# Output_channel.net
KiCad netlist of a schematic drawn in Altium Designer
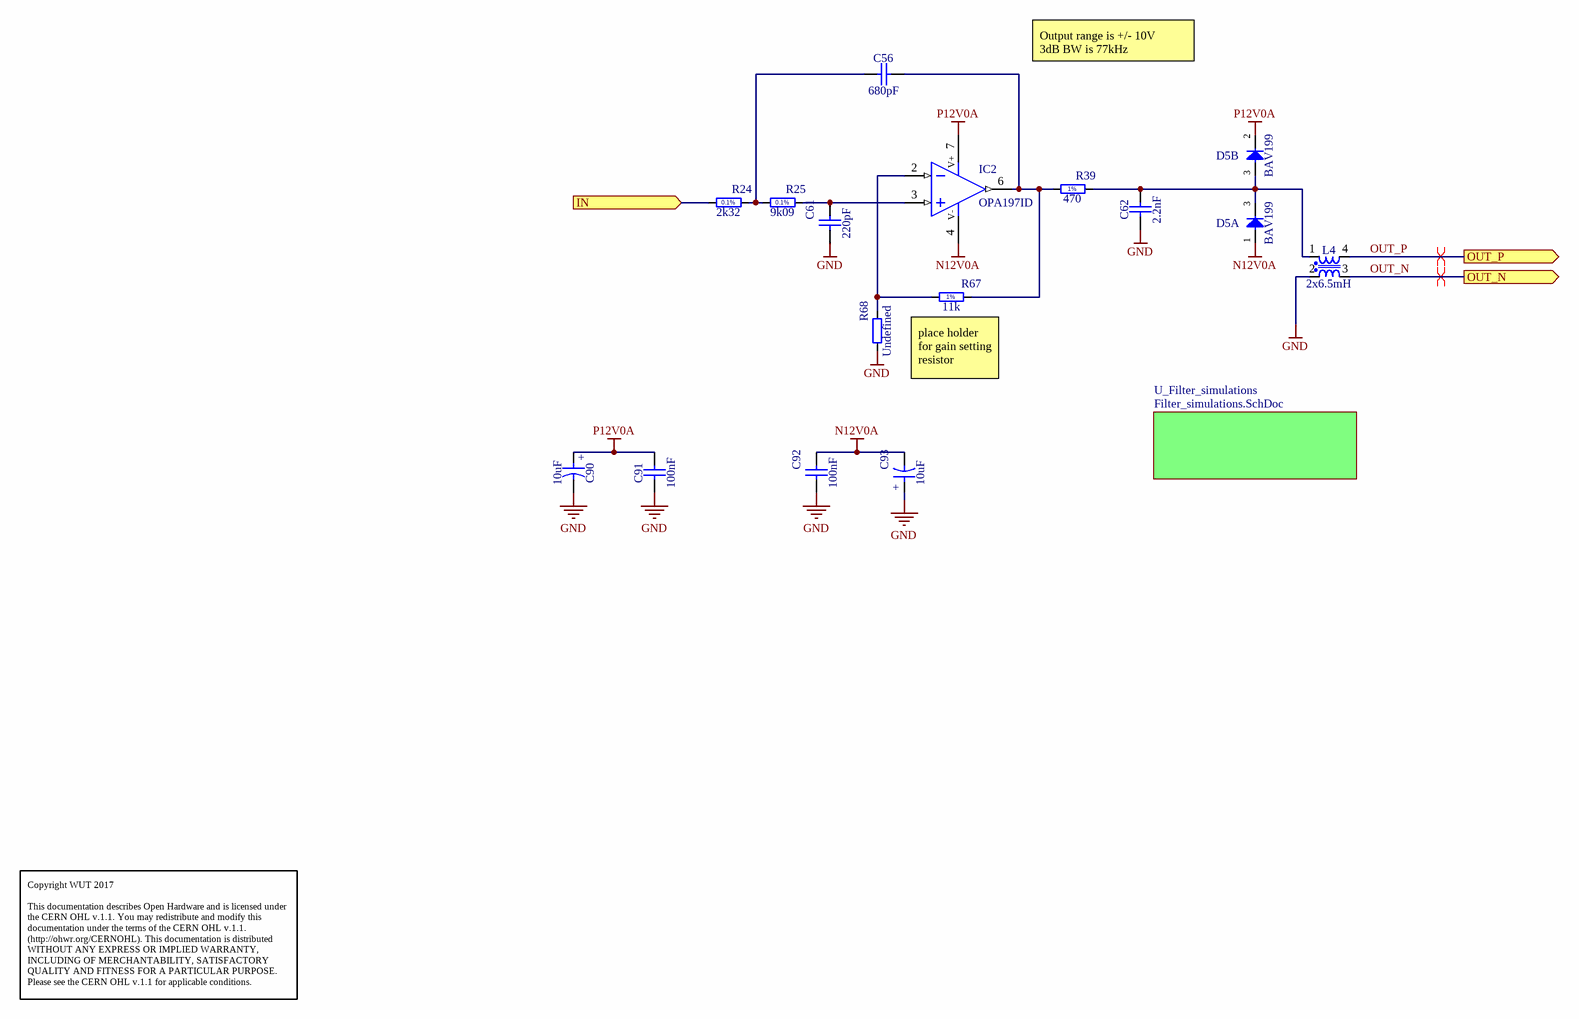
[diagram p0: Output_channel.SchDoc]

(export (version "E")
  (design (tool "Eeschema 10.0.6"))
  (components
    (comp (ref "C56")
      (value "680pF")
      (footprint "CAPC2012X135N")
      (description "Non-polarised capacitor")
      (fields
        (field (name "PART NUMBER") "CC0805_680PF_50V_5%_NP0")
        (field (name "VOLTAGE") "50V")
        (field (name "AUTHOR") "CERN DEM JLC")
      )
      (libsource (lib "Capacitors") (part "Capacitor - non polarized"))
    )
    (comp (ref "C61")
      (value "220pF")
      (footprint "CAPC1608X87N")
      (description "Non-polarised capacitor")
      (fields
        (field (name "PART NUMBER") "CC0603_220PF_50V_5%_NP0")
        (field (name "VOLTAGE") "50V")
        (field (name "AUTHOR") "CERN DEM JLC")
      )
      (libsource (lib "Capacitors") (part "Capacitor - non polarized"))
    )
    (comp (ref "C62")
      (value "2.2nF")
      (footprint "CAPC3216X140N")
      (description "Non-polarised capacitor")
      (fields
        (field (name "PART NUMBER") "CC1206_2.2NF_50V_5%_NP0")
        (field (name "VOLTAGE") "50V")
        (field (name "AUTHOR") "CERN DEM JLC")
      )
      (libsource (lib "Capacitors") (part "Capacitor - non polarized"))
    )
    (comp (ref "C90")
      (value "10uF")
      (footprint "CAPMP3216X180N")
      (description "Polarised capacitor")
      (fields
        (field (name "PART NUMBER") "CTE3216-18_10UF_16V_20%_AVX_TCJ")
        (field (name "VOLTAGE") "16V")
        (field (name "AUTHOR") "CERN DEM JLC")
      )
      (libsource (lib "Capacitors") (part "Capacitor - polarized"))
    )
    (comp (ref "C91")
      (value "100nF")
      (footprint "CAPC1005X55N")
      (description "Non-polarised capacitor")
      (fields
        (field (name "PART NUMBER") "CC0402_100NF_16V_10%_X7R")
        (field (name "VOLTAGE") "16V")
        (field (name "AUTHOR") "CERN DEM JLC")
      )
      (libsource (lib "Capacitors") (part "Capacitor - non polarized"))
    )
    (comp (ref "C92")
      (value "100nF")
      (footprint "CAPC1005X55N")
      (description "Non-polarised capacitor")
      (fields
        (field (name "PART NUMBER") "CC0402_100NF_16V_10%_X7R")
        (field (name "VOLTAGE") "16V")
        (field (name "AUTHOR") "CERN DEM JLC")
      )
      (libsource (lib "Capacitors") (part "Capacitor - non polarized"))
    )
    (comp (ref "C93")
      (value "10uF")
      (footprint "CAPMP3216X180N")
      (description "Polarised capacitor")
      (fields
        (field (name "PART NUMBER") "CTE3216-18_10UF_16V_20%_AVX_TCJ")
        (field (name "VOLTAGE") "16V")
        (field (name "AUTHOR") "CERN DEM JLC")
      )
      (libsource (lib "Capacitors") (part "Capacitor - polarized"))
    )
    (comp (ref "D5")
      (value "BAV199")
      (footprint "SOT95P240X110-3N")
      (description "Serial Diode")
      (fields
        (field (name "VOLTAGE") "75V")
        (field (name "POWER") "250mW")
        (field (name "AUTHOR") "CERN DEM JMW")
      )
      (libsource (lib "ICs And Semiconductors") (part "Diode x2 A1C3_A3C2"))
    )
    (comp (ref "IC2")
      (value "OPA197ID")
      (footprint "SOIC127P600X175-8N")
      (description "36-V, Precision, Rail-to-Rail Input/Output, Low Offset Voltage, Operational Amplifiers")
      (fields (field (name "MANUFACTURER") "TEXAS INSTRUMENTS") (field (name "AUTHOR") "GK"))
      (libsource (lib "LIBRARY_SCH") (part "OA_OPA197"))
    )
    (comp (ref "L4")
      (value "2x6.5mH")
      (footprint "IND_WURTH_WE-SL2")
      (description "Inductor Common Mode")
      (fields
        (field (name "PART NUMBER") "IND_6.5MH_50%_WURTH_WE-SL2-744229")
        (field (name "POWER") "400mA")
        (field (name "AUTHOR") "CERN DEM JLC")
      )
      (libsource (lib "Inductors & Transformers") (part "Inductor Common Mode 1Dot-4 2Dot-3"))
    )
    (comp (ref "R24")
      (value "2k32")
      (footprint "RESC1608X55N")
      (description "Resistor - 0.1%")
      (fields
        (field (name "PART NUMBER") "R0603_2K32_0.1%_0.063W_10PPM")
        (field (name "POWER") "0.063W")
        (field (name "AUTHOR") "CERN DEM JLC")
      )
      (libsource (lib "Resistors") (part "Resistor - 0.1%"))
    )
    (comp (ref "R25")
      (value "9k09")
      (footprint "RESC1608X55N")
      (description "Resistor - 0.1%")
      (fields
        (field (name "PART NUMBER") "R0603_9K09_0.1%_0.063W_10PPM")
        (field (name "POWER") "0.063W")
        (field (name "AUTHOR") "CERN DEM JLC")
      )
      (libsource (lib "Resistors") (part "Resistor - 0.1%"))
    )
    (comp (ref "R39")
      (value "470")
      (footprint "RESC1608X55N")
      (description "Resistor - 1%")
      (fields
        (field (name "PART NUMBER") "R0603_470R_1%_0.1W_100PPM")
        (field (name "POWER") "0.1W")
        (field (name "AUTHOR") "CERN DEM JLC")
      )
      (libsource (lib "Resistors") (part "Resistor - 1%"))
    )
    (comp (ref "R67")
      (value "11k")
      (footprint "RESC1608X55N")
      (description "Resistor - 1%")
      (fields
        (field (name "PART NUMBER") "R0603_11K_1%_0.1W_100PPM")
        (field (name "POWER") "0.1W")
        (field (name "AUTHOR") "CERN DEM JLC")
      )
      (libsource (lib "Resistors") (part "Resistor - 1%"))
    )
    (comp (ref "R68")
      (value "Undefined")
      (footprint "RESC1608X55N")
      (description "Resistor")
      (fields (field (name "PART NUMBER") "R0603_NO-VALUE") (field (name "AUTHOR") "CERN DEM JLC"))
      (libsource (lib "Resistors") (part "Resistor"))
    )
  )
  (nets
    (net (code "1") (name "/IN") (class "Default")
      (node (ref "R24") (pin "1") (pinfunction "1_1") (pintype "passive"))
    )
    (net (code "2") (name "/OUT_N") (class "Default")
      (node (ref "L4") (pin "3") (pinfunction "3_3") (pintype "passive"))
    )
    (net (code "3") (name "/OUT_P") (class "Default")
      (node (ref "L4") (pin "4") (pinfunction "4_4") (pintype "passive"))
    )
    (net (code "4") (name "GND") (class "Default")
      (node (ref "C61") (pin "1") (pinfunction "1_1") (pintype "passive"))
      (node (ref "C62") (pin "1") (pinfunction "1_1") (pintype "passive"))
      (node (ref "C90") (pin "2") (pinfunction "2_2") (pintype "passive"))
      (node (ref "C91") (pin "1") (pinfunction "1_1") (pintype "passive"))
      (node (ref "C92") (pin "1") (pinfunction "1_1") (pintype "passive"))
      (node (ref "C93") (pin "1") (pinfunction "1_1") (pintype "passive"))
      (node (ref "L4") (pin "2") (pinfunction "2_2") (pintype "passive"))
      (node (ref "R68") (pin "1") (pinfunction "1_1") (pintype "passive"))
    )
    (net (code "5") (name "N12V0A") (class "Default")
      (node (ref "C92") (pin "2") (pinfunction "2_2") (pintype "passive"))
      (node (ref "C93") (pin "2") (pinfunction "2_2") (pintype "passive"))
      (node (ref "D5") (pin "1") (pinfunction "A_1") (pintype "passive"))
      (node (ref "IC2") (pin "4") (pinfunction "V-_4") (pintype "power_in"))
    )
    (net (code "6") (name "Net-(C56-Pad1)") (class "Default")
      (node (ref "C56") (pin "1") (pinfunction "1_1") (pintype "passive"))
      (node (ref "R24") (pin "2") (pinfunction "2_2") (pintype "passive"))
      (node (ref "R25") (pin "1") (pinfunction "1_1") (pintype "passive"))
    )
    (net (code "7") (name "Net-(D5A-COMAC)") (class "Default")
      (node (ref "C62") (pin "2") (pinfunction "2_2") (pintype "passive"))
      (node (ref "D5") (pin "3") (pinfunction "COMAC_3") (pintype "passive"))
      (node (ref "L4") (pin "1") (pinfunction "1_1") (pintype "passive"))
      (node (ref "R39") (pin "2") (pinfunction "2_2") (pintype "passive"))
    )
    (net (code "8") (name "Net-(IC2-IN+)") (class "Default")
      (node (ref "C61") (pin "2") (pinfunction "2_2") (pintype "passive"))
      (node (ref "IC2") (pin "3") (pinfunction "IN+_3") (pintype "input"))
      (node (ref "R25") (pin "2") (pinfunction "2_2") (pintype "passive"))
    )
    (net (code "9") (name "Net-(IC2-IN-)") (class "Default")
      (node (ref "IC2") (pin "2") (pinfunction "IN-_2") (pintype "input"))
      (node (ref "R67") (pin "1") (pinfunction "1_1") (pintype "passive"))
      (node (ref "R68") (pin "2") (pinfunction "2_2") (pintype "passive"))
    )
    (net (code "10") (name "Net-(IC2-OUT)") (class "Default")
      (node (ref "C56") (pin "2") (pinfunction "2_2") (pintype "passive"))
      (node (ref "IC2") (pin "6") (pinfunction "OUT_6") (pintype "output"))
      (node (ref "R39") (pin "1") (pinfunction "1_1") (pintype "passive"))
      (node (ref "R67") (pin "2") (pinfunction "2_2") (pintype "passive"))
    )
    (net (code "11") (name "P12V0A") (class "Default")
      (node (ref "C90") (pin "1") (pinfunction "1_1") (pintype "passive"))
      (node (ref "C91") (pin "2") (pinfunction "2_2") (pintype "passive"))
      (node (ref "D5") (pin "2") (pinfunction "C_2") (pintype "passive"))
      (node (ref "IC2") (pin "7") (pinfunction "V+_7") (pintype "power_in"))
    )
  )
)
